# DSP_connectors.net
KiCad netlist of a schematic drawn in Altium Designer
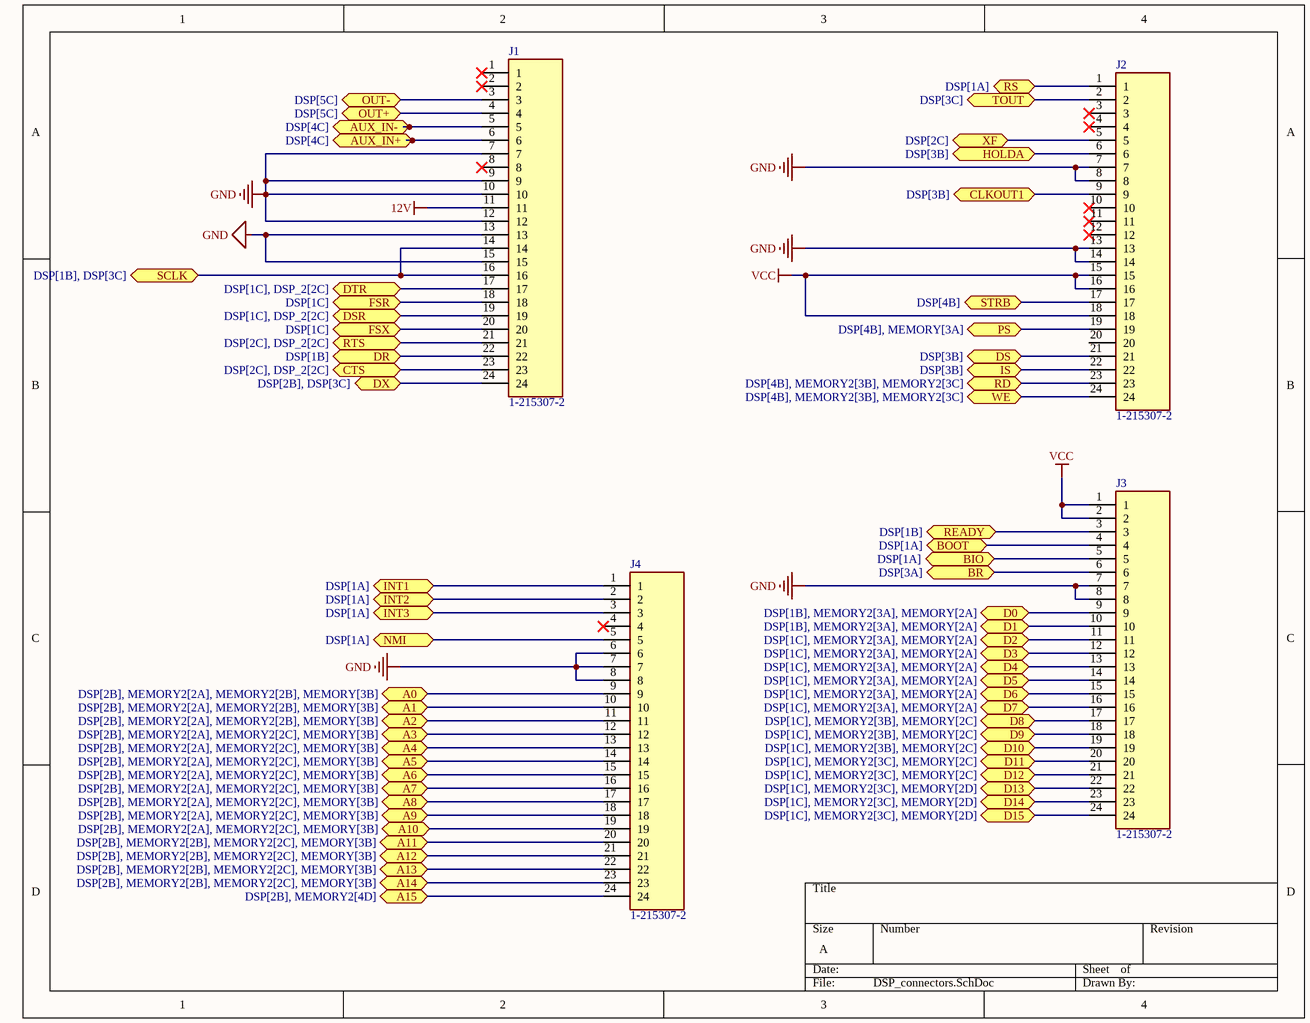
[diagram p0: DSP_connectors.SchDoc]

(export (version "E")
  (design (tool "Eeschema 10.0.6"))
  (components
    (comp (ref "J1")
      (value "1-215307-2")
      (footprint "TE_1-215307-2")
      (libsource (lib "1-215307-2") (part "1-215307-2"))
    )
    (comp (ref "J2")
      (value "1-215307-2")
      (footprint "TE_1-215307-2")
      (libsource (lib "1-215307-2") (part "1-215307-2"))
    )
    (comp (ref "J3")
      (value "1-215307-2")
      (footprint "TE_1-215307-2")
      (libsource (lib "1-215307-2") (part "1-215307-2"))
    )
    (comp (ref "J4")
      (value "1-215307-2")
      (footprint "TE_1-215307-2")
      (libsource (lib "1-215307-2") (part "1-215307-2"))
    )
  )
  (nets
    (net (code "1") (name "/A0") (class "Default")
      (node (ref "J4") (pin "9") (pinfunction "9_9") (pintype "passive"))
    )
    (net (code "2") (name "/A1") (class "Default")
      (node (ref "J4") (pin "10") (pinfunction "10_10") (pintype "passive"))
    )
    (net (code "3") (name "/A2") (class "Default")
      (node (ref "J4") (pin "11") (pinfunction "11_11") (pintype "passive"))
    )
    (net (code "4") (name "/A3") (class "Default")
      (node (ref "J4") (pin "12") (pinfunction "12_12") (pintype "passive"))
    )
    (net (code "5") (name "/A4") (class "Default")
      (node (ref "J4") (pin "13") (pinfunction "13_13") (pintype "passive"))
    )
    (net (code "6") (name "/A5") (class "Default")
      (node (ref "J4") (pin "14") (pinfunction "14_14") (pintype "passive"))
    )
    (net (code "7") (name "/A6") (class "Default")
      (node (ref "J4") (pin "15") (pinfunction "15_15") (pintype "passive"))
    )
    (net (code "8") (name "/A7") (class "Default")
      (node (ref "J4") (pin "16") (pinfunction "16_16") (pintype "passive"))
    )
    (net (code "9") (name "/A8") (class "Default")
      (node (ref "J4") (pin "17") (pinfunction "17_17") (pintype "passive"))
    )
    (net (code "10") (name "/A9") (class "Default")
      (node (ref "J4") (pin "18") (pinfunction "18_18") (pintype "passive"))
    )
    (net (code "11") (name "/A10") (class "Default")
      (node (ref "J4") (pin "19") (pinfunction "19_19") (pintype "passive"))
    )
    (net (code "12") (name "/A11") (class "Default")
      (node (ref "J4") (pin "20") (pinfunction "20_20") (pintype "passive"))
    )
    (net (code "13") (name "/A12") (class "Default")
      (node (ref "J4") (pin "21") (pinfunction "21_21") (pintype "passive"))
    )
    (net (code "14") (name "/A13") (class "Default")
      (node (ref "J4") (pin "22") (pinfunction "22_22") (pintype "passive"))
    )
    (net (code "15") (name "/A14") (class "Default")
      (node (ref "J4") (pin "23") (pinfunction "23_23") (pintype "passive"))
    )
    (net (code "16") (name "/A15") (class "Default")
      (node (ref "J4") (pin "24") (pinfunction "24_24") (pintype "passive"))
    )
    (net (code "17") (name "/AUX_IN+") (class "Default")
      (node (ref "J1") (pin "6") (pinfunction "6_6") (pintype "passive"))
    )
    (net (code "18") (name "/AUX_IN-") (class "Default")
      (node (ref "J1") (pin "5") (pinfunction "5_5") (pintype "passive"))
    )
    (net (code "19") (name "/BIO") (class "Default")
      (node (ref "J3") (pin "5") (pinfunction "5_5") (pintype "passive"))
    )
    (net (code "20") (name "/BOOT") (class "Default")
      (node (ref "J3") (pin "4") (pinfunction "4_4") (pintype "passive"))
    )
    (net (code "21") (name "/BR") (class "Default")
      (node (ref "J3") (pin "6") (pinfunction "6_6") (pintype "passive"))
    )
    (net (code "22") (name "/CLKOUT1") (class "Default")
      (node (ref "J2") (pin "9") (pinfunction "9_9") (pintype "passive"))
    )
    (net (code "23") (name "/CTS") (class "Default")
      (node (ref "J1") (pin "23") (pinfunction "23_23") (pintype "passive"))
    )
    (net (code "24") (name "/D0") (class "Default")
      (node (ref "J3") (pin "9") (pinfunction "9_9") (pintype "passive"))
    )
    (net (code "25") (name "/D1") (class "Default")
      (node (ref "J3") (pin "10") (pinfunction "10_10") (pintype "passive"))
    )
    (net (code "26") (name "/D2") (class "Default")
      (node (ref "J3") (pin "11") (pinfunction "11_11") (pintype "passive"))
    )
    (net (code "27") (name "/D3") (class "Default")
      (node (ref "J3") (pin "12") (pinfunction "12_12") (pintype "passive"))
    )
    (net (code "28") (name "/D4") (class "Default")
      (node (ref "J3") (pin "13") (pinfunction "13_13") (pintype "passive"))
    )
    (net (code "29") (name "/D5") (class "Default")
      (node (ref "J3") (pin "14") (pinfunction "14_14") (pintype "passive"))
    )
    (net (code "30") (name "/D6") (class "Default")
      (node (ref "J3") (pin "15") (pinfunction "15_15") (pintype "passive"))
    )
    (net (code "31") (name "/D7") (class "Default")
      (node (ref "J3") (pin "16") (pinfunction "16_16") (pintype "passive"))
    )
    (net (code "32") (name "/D8") (class "Default")
      (node (ref "J3") (pin "17") (pinfunction "17_17") (pintype "passive"))
    )
    (net (code "33") (name "/D9") (class "Default")
      (node (ref "J3") (pin "18") (pinfunction "18_18") (pintype "passive"))
    )
    (net (code "34") (name "/D10") (class "Default")
      (node (ref "J3") (pin "19") (pinfunction "19_19") (pintype "passive"))
    )
    (net (code "35") (name "/D11") (class "Default")
      (node (ref "J3") (pin "20") (pinfunction "20_20") (pintype "passive"))
    )
    (net (code "36") (name "/D12") (class "Default")
      (node (ref "J3") (pin "21") (pinfunction "21_21") (pintype "passive"))
    )
    (net (code "37") (name "/D13") (class "Default")
      (node (ref "J3") (pin "22") (pinfunction "22_22") (pintype "passive"))
    )
    (net (code "38") (name "/D14") (class "Default")
      (node (ref "J3") (pin "23") (pinfunction "23_23") (pintype "passive"))
    )
    (net (code "39") (name "/D15") (class "Default")
      (node (ref "J3") (pin "24") (pinfunction "24_24") (pintype "passive"))
    )
    (net (code "40") (name "/DR") (class "Default")
      (node (ref "J1") (pin "22") (pinfunction "22_22") (pintype "passive"))
    )
    (net (code "41") (name "/DS") (class "Default")
      (node (ref "J2") (pin "21") (pinfunction "21_21") (pintype "passive"))
    )
    (net (code "42") (name "/DSR") (class "Default")
      (node (ref "J1") (pin "19") (pinfunction "19_19") (pintype "passive"))
    )
    (net (code "43") (name "/DTR") (class "Default")
      (node (ref "J1") (pin "17") (pinfunction "17_17") (pintype "passive"))
    )
    (net (code "44") (name "/DX") (class "Default")
      (node (ref "J1") (pin "24") (pinfunction "24_24") (pintype "passive"))
    )
    (net (code "45") (name "/FSR") (class "Default")
      (node (ref "J1") (pin "18") (pinfunction "18_18") (pintype "passive"))
    )
    (net (code "46") (name "/FSX") (class "Default")
      (node (ref "J1") (pin "20") (pinfunction "20_20") (pintype "passive"))
    )
    (net (code "47") (name "/HOLDA") (class "Default")
      (node (ref "J2") (pin "6") (pinfunction "6_6") (pintype "passive"))
    )
    (net (code "48") (name "/INT1") (class "Default")
      (node (ref "J4") (pin "1") (pinfunction "1_1") (pintype "passive"))
    )
    (net (code "49") (name "/INT2") (class "Default")
      (node (ref "J4") (pin "2") (pinfunction "2_2") (pintype "passive"))
    )
    (net (code "50") (name "/INT3") (class "Default")
      (node (ref "J4") (pin "3") (pinfunction "3_3") (pintype "passive"))
    )
    (net (code "51") (name "/IS") (class "Default")
      (node (ref "J2") (pin "22") (pinfunction "22_22") (pintype "passive"))
    )
    (net (code "52") (name "/NMI") (class "Default")
      (node (ref "J4") (pin "5") (pinfunction "5_5") (pintype "passive"))
    )
    (net (code "53") (name "/OUT+") (class "Default")
      (node (ref "J1") (pin "4") (pinfunction "4_4") (pintype "passive"))
    )
    (net (code "54") (name "/OUT-") (class "Default")
      (node (ref "J1") (pin "3") (pinfunction "3_3") (pintype "passive"))
    )
    (net (code "55") (name "/PS") (class "Default")
      (node (ref "J2") (pin "19") (pinfunction "19_19") (pintype "passive"))
    )
    (net (code "56") (name "/RD") (class "Default")
      (node (ref "J2") (pin "23") (pinfunction "23_23") (pintype "passive"))
    )
    (net (code "57") (name "/READY") (class "Default")
      (node (ref "J3") (pin "3") (pinfunction "3_3") (pintype "passive"))
    )
    (net (code "58") (name "/RS") (class "Default")
      (node (ref "J2") (pin "1") (pinfunction "1_1") (pintype "passive"))
    )
    (net (code "59") (name "/RTS") (class "Default")
      (node (ref "J1") (pin "21") (pinfunction "21_21") (pintype "passive"))
    )
    (net (code "60") (name "/SCLK") (class "Default")
      (node (ref "J1") (pin "14") (pinfunction "14_14") (pintype "passive"))
      (node (ref "J1") (pin "16") (pinfunction "16_16") (pintype "passive"))
    )
    (net (code "61") (name "/STRB") (class "Default")
      (node (ref "J2") (pin "17") (pinfunction "17_17") (pintype "passive"))
    )
    (net (code "62") (name "/TOUT") (class "Default")
      (node (ref "J2") (pin "2") (pinfunction "2_2") (pintype "passive"))
    )
    (net (code "63") (name "/WE") (class "Default")
      (node (ref "J2") (pin "24") (pinfunction "24_24") (pintype "passive"))
    )
    (net (code "64") (name "/XF") (class "Default")
      (node (ref "J2") (pin "5") (pinfunction "5_5") (pintype "passive"))
    )
    (net (code "65") (name "12V") (class "Default")
      (node (ref "J1") (pin "11") (pinfunction "11_11") (pintype "passive"))
    )
    (net (code "66") (name "GND") (class "Default")
      (node (ref "J1") (pin "10") (pinfunction "10_10") (pintype "passive"))
      (node (ref "J1") (pin "12") (pinfunction "12_12") (pintype "passive"))
      (node (ref "J1") (pin "13") (pinfunction "13_13") (pintype "passive"))
      (node (ref "J1") (pin "15") (pinfunction "15_15") (pintype "passive"))
      (node (ref "J1") (pin "7") (pinfunction "7_7") (pintype "passive"))
      (node (ref "J1") (pin "9") (pinfunction "9_9") (pintype "passive"))
      (node (ref "J2") (pin "13") (pinfunction "13_13") (pintype "passive"))
      (node (ref "J2") (pin "14") (pinfunction "14_14") (pintype "passive"))
      (node (ref "J2") (pin "7") (pinfunction "7_7") (pintype "passive"))
      (node (ref "J2") (pin "8") (pinfunction "8_8") (pintype "passive"))
      (node (ref "J3") (pin "7") (pinfunction "7_7") (pintype "passive"))
      (node (ref "J3") (pin "8") (pinfunction "8_8") (pintype "passive"))
      (node (ref "J4") (pin "6") (pinfunction "6_6") (pintype "passive"))
      (node (ref "J4") (pin "7") (pinfunction "7_7") (pintype "passive"))
      (node (ref "J4") (pin "8") (pinfunction "8_8") (pintype "passive"))
    )
    (net (code "67") (name "VCC") (class "Default")
      (node (ref "J2") (pin "15") (pinfunction "15_15") (pintype "passive"))
      (node (ref "J2") (pin "16") (pinfunction "16_16") (pintype "passive"))
      (node (ref "J2") (pin "18") (pinfunction "18_18") (pintype "passive"))
      (node (ref "J3") (pin "1") (pinfunction "1_1") (pintype "passive"))
      (node (ref "J3") (pin "2") (pinfunction "2_2") (pintype "passive"))
    )
    (net (code "68") (name "unconnected-(J1-Pad1)") (class "Default")
      (node (ref "J1") (pin "1") (pinfunction "1_1") (pintype "passive+no_connect"))
    )
    (net (code "69") (name "unconnected-(J1-Pad2)") (class "Default")
      (node (ref "J1") (pin "2") (pinfunction "2_2") (pintype "passive+no_connect"))
    )
    (net (code "70") (name "unconnected-(J1-Pad8)") (class "Default")
      (node (ref "J1") (pin "8") (pinfunction "8_8") (pintype "passive+no_connect"))
    )
    (net (code "71") (name "unconnected-(J2-Pad3)") (class "Default")
      (node (ref "J2") (pin "3") (pinfunction "3_3") (pintype "passive+no_connect"))
    )
    (net (code "72") (name "unconnected-(J2-Pad4)") (class "Default")
      (node (ref "J2") (pin "4") (pinfunction "4_4") (pintype "passive+no_connect"))
    )
    (net (code "73") (name "unconnected-(J2-Pad10)") (class "Default")
      (node (ref "J2") (pin "10") (pinfunction "10_10") (pintype "passive+no_connect"))
    )
    (net (code "74") (name "unconnected-(J2-Pad11)") (class "Default")
      (node (ref "J2") (pin "11") (pinfunction "11_11") (pintype "passive+no_connect"))
    )
    (net (code "75") (name "unconnected-(J2-Pad12)") (class "Default")
      (node (ref "J2") (pin "12") (pinfunction "12_12") (pintype "passive+no_connect"))
    )
    (net (code "76") (name "unconnected-(J2-Pad20)") (class "Default")
      (node (ref "J2") (pin "20") (pinfunction "20_20") (pintype "passive"))
    )
    (net (code "77") (name "unconnected-(J4-Pad4)") (class "Default")
      (node (ref "J4") (pin "4") (pinfunction "4_4") (pintype "passive+no_connect"))
    )
  )
)
